# dht22ow3.net
KiCad netlist of a schematic drawn in EAGLE
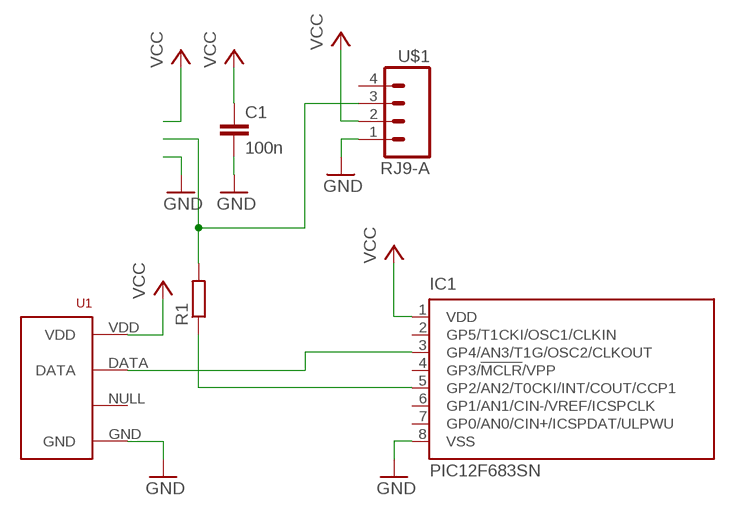
[diagram p0: schematic, sheet 1]

(export (version "E")
  (design (tool "Eeschema 10.0.6"))
  (components
    (comp (ref "C1")
      (value "100n")
      (footprint "eagle-import:C1206")
      (libsource (lib "eagle-import") (part "C-EUC1206"))
    )
    (comp (ref "IC1")
      (value "PIC12F683SN")
      (footprint "eagle-import:SO-08")
      (fields (field (name "MF") "MICROCHIP") (field (name "MPN") "PIC12F683-I/SN"))
      (libsource (lib "eagle-import") (part "PIC12F683SN"))
    )
    (comp (ref "R1")
      (value "R-EU_R1206")
      (footprint "eagle-import:R1206")
      (libsource (lib "eagle-import") (part "R-EU_R1206"))
    )
    (comp (ref "U$1")
      (value "RJ9-A")
      (footprint "eagle-import:RJ9-A")
      (libsource (lib "eagle-import") (part "RJ9-A"))
    )
    (comp (ref "U1")
      (value "RHT03_DHT-22_AM2302RA")
      (footprint "eagle-import:RHT03_DHT-22_RA")
      (libsource (lib "eagle-import") (part "RHT03_DHT-22_AM2302RA"))
    )
  )
  (nets
    (net (code "1") (name "GND") (class "Default")
      (node (ref "C1") (pin "2") (pinfunction "2_2") (pintype "passive"))
      (node (ref "IC1") (pin "8") (pinfunction "VSS_8") (pintype "power_in"))
      (node (ref "U$1") (pin "1") (pinfunction "1_1") (pintype "passive"))
      (node (ref "U1") (pin "GND") (pinfunction "GND_GND") (pintype "power_in"))
    )
    (net (code "2") (name "Net-(IC1-GP2{slash}AN2{slash}T0CKI{slash}INT{slash}COUT{slash}CCP1)") (class "Default")
      (node (ref "IC1") (pin "5") (pinfunction "GP2/AN2/T0CKI/INT/COUT/CCP1_5") (pintype "bidirectional"))
      (node (ref "R1") (pin "1") (pinfunction "1_1") (pintype "passive"))
    )
    (net (code "3") (name "Net-(IC1-GP4{slash}AN3{slash}T1G{slash}OSC2{slash}CLKOUT)") (class "Default")
      (node (ref "IC1") (pin "3") (pinfunction "GP4/AN3/T1G/OSC2/CLKOUT_3") (pintype "bidirectional"))
      (node (ref "U1") (pin "DATA") (pinfunction "DATA_DATA") (pintype "bidirectional"))
    )
    (net (code "4") (name "Net-(R1-Pad2)") (class "Default")
      (node (ref "R1") (pin "2") (pinfunction "2_2") (pintype "passive"))
      (node (ref "U$1") (pin "3") (pinfunction "3_3") (pintype "passive"))
    )
    (net (code "5") (name "VCC") (class "Default")
      (node (ref "C1") (pin "1") (pinfunction "1_1") (pintype "passive"))
      (node (ref "IC1") (pin "1") (pinfunction "VDD_1") (pintype "power_in"))
      (node (ref "U$1") (pin "2") (pinfunction "2_2") (pintype "passive"))
      (node (ref "U1") (pin "VDD") (pinfunction "VDD_VDD") (pintype "power_in"))
    )
    (net (code "6") (name "unconnected-(IC1-GP0{slash}AN0{slash}CIN+{slash}ICSPDAT{slash}ULPWU-Pad7)") (class "Default")
      (node (ref "IC1") (pin "7") (pinfunction "GP0/AN0/CIN+/ICSPDAT/ULPWU_7") (pintype "bidirectional"))
    )
    (net (code "7") (name "unconnected-(IC1-GP1{slash}AN1{slash}CIN-{slash}VREF{slash}ICSPCLK-Pad6)") (class "Default")
      (node (ref "IC1") (pin "6") (pinfunction "GP1/AN1/CIN-/VREF/ICSPCLK_6") (pintype "bidirectional"))
    )
    (net (code "8") (name "unconnected-(IC1-GP3{slash}~{MCLR}{slash}VPP-Pad4)") (class "Default")
      (node (ref "IC1") (pin "4") (pinfunction "GP3/~{MCLR}/VPP_4") (pintype "bidirectional"))
    )
    (net (code "9") (name "unconnected-(IC1-GP5{slash}T1CKI{slash}OSC1{slash}CLKIN-Pad2)") (class "Default")
      (node (ref "IC1") (pin "2") (pinfunction "GP5/T1CKI/OSC1/CLKIN_2") (pintype "bidirectional"))
    )
    (net (code "10") (name "unconnected-(U$1-Pad4)") (class "Default")
      (node (ref "U$1") (pin "4") (pinfunction "4_4") (pintype "passive"))
    )
    (net (code "11") (name "unconnected-(U1-PadNULL)") (class "Default")
      (node (ref "U1") (pin "NULL") (pinfunction "NULL_NULL") (pintype "no_connect"))
    )
  )
)
